# ETH-IO_v2_1.net
KiCad netlist of a schematic drawn in EAGLE
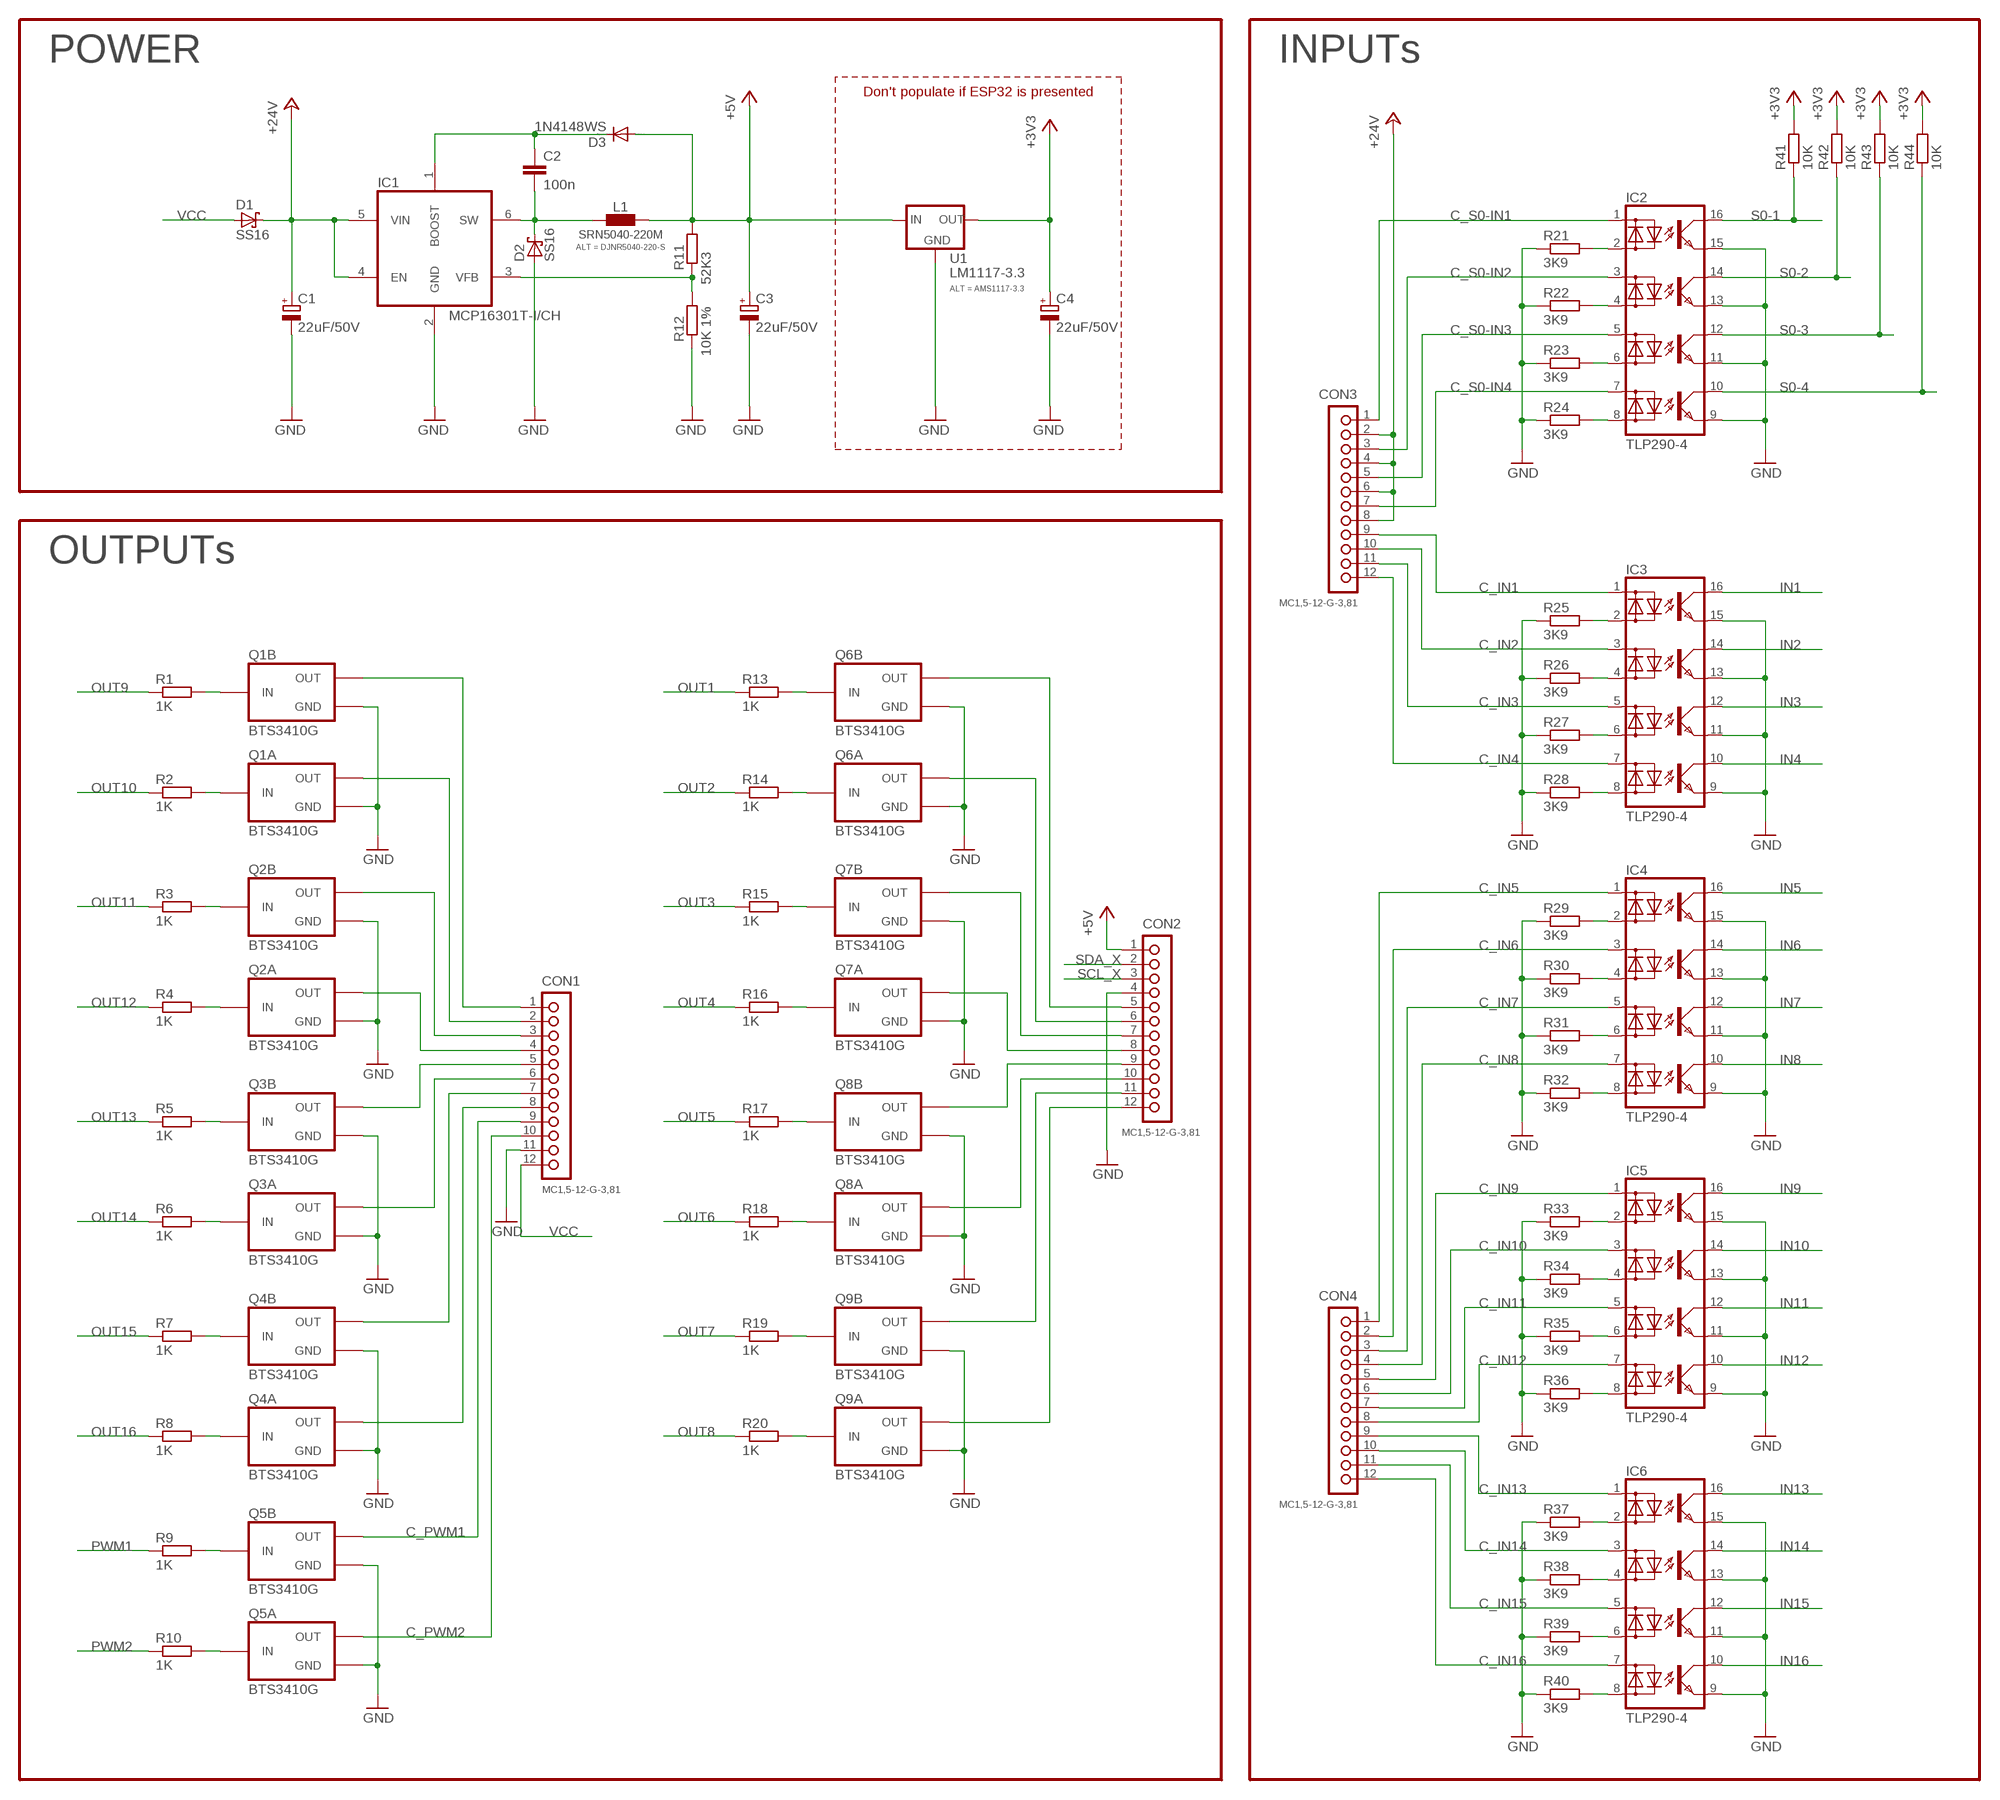
[diagram p0: schematic, sheet 1, part 1 of 2]
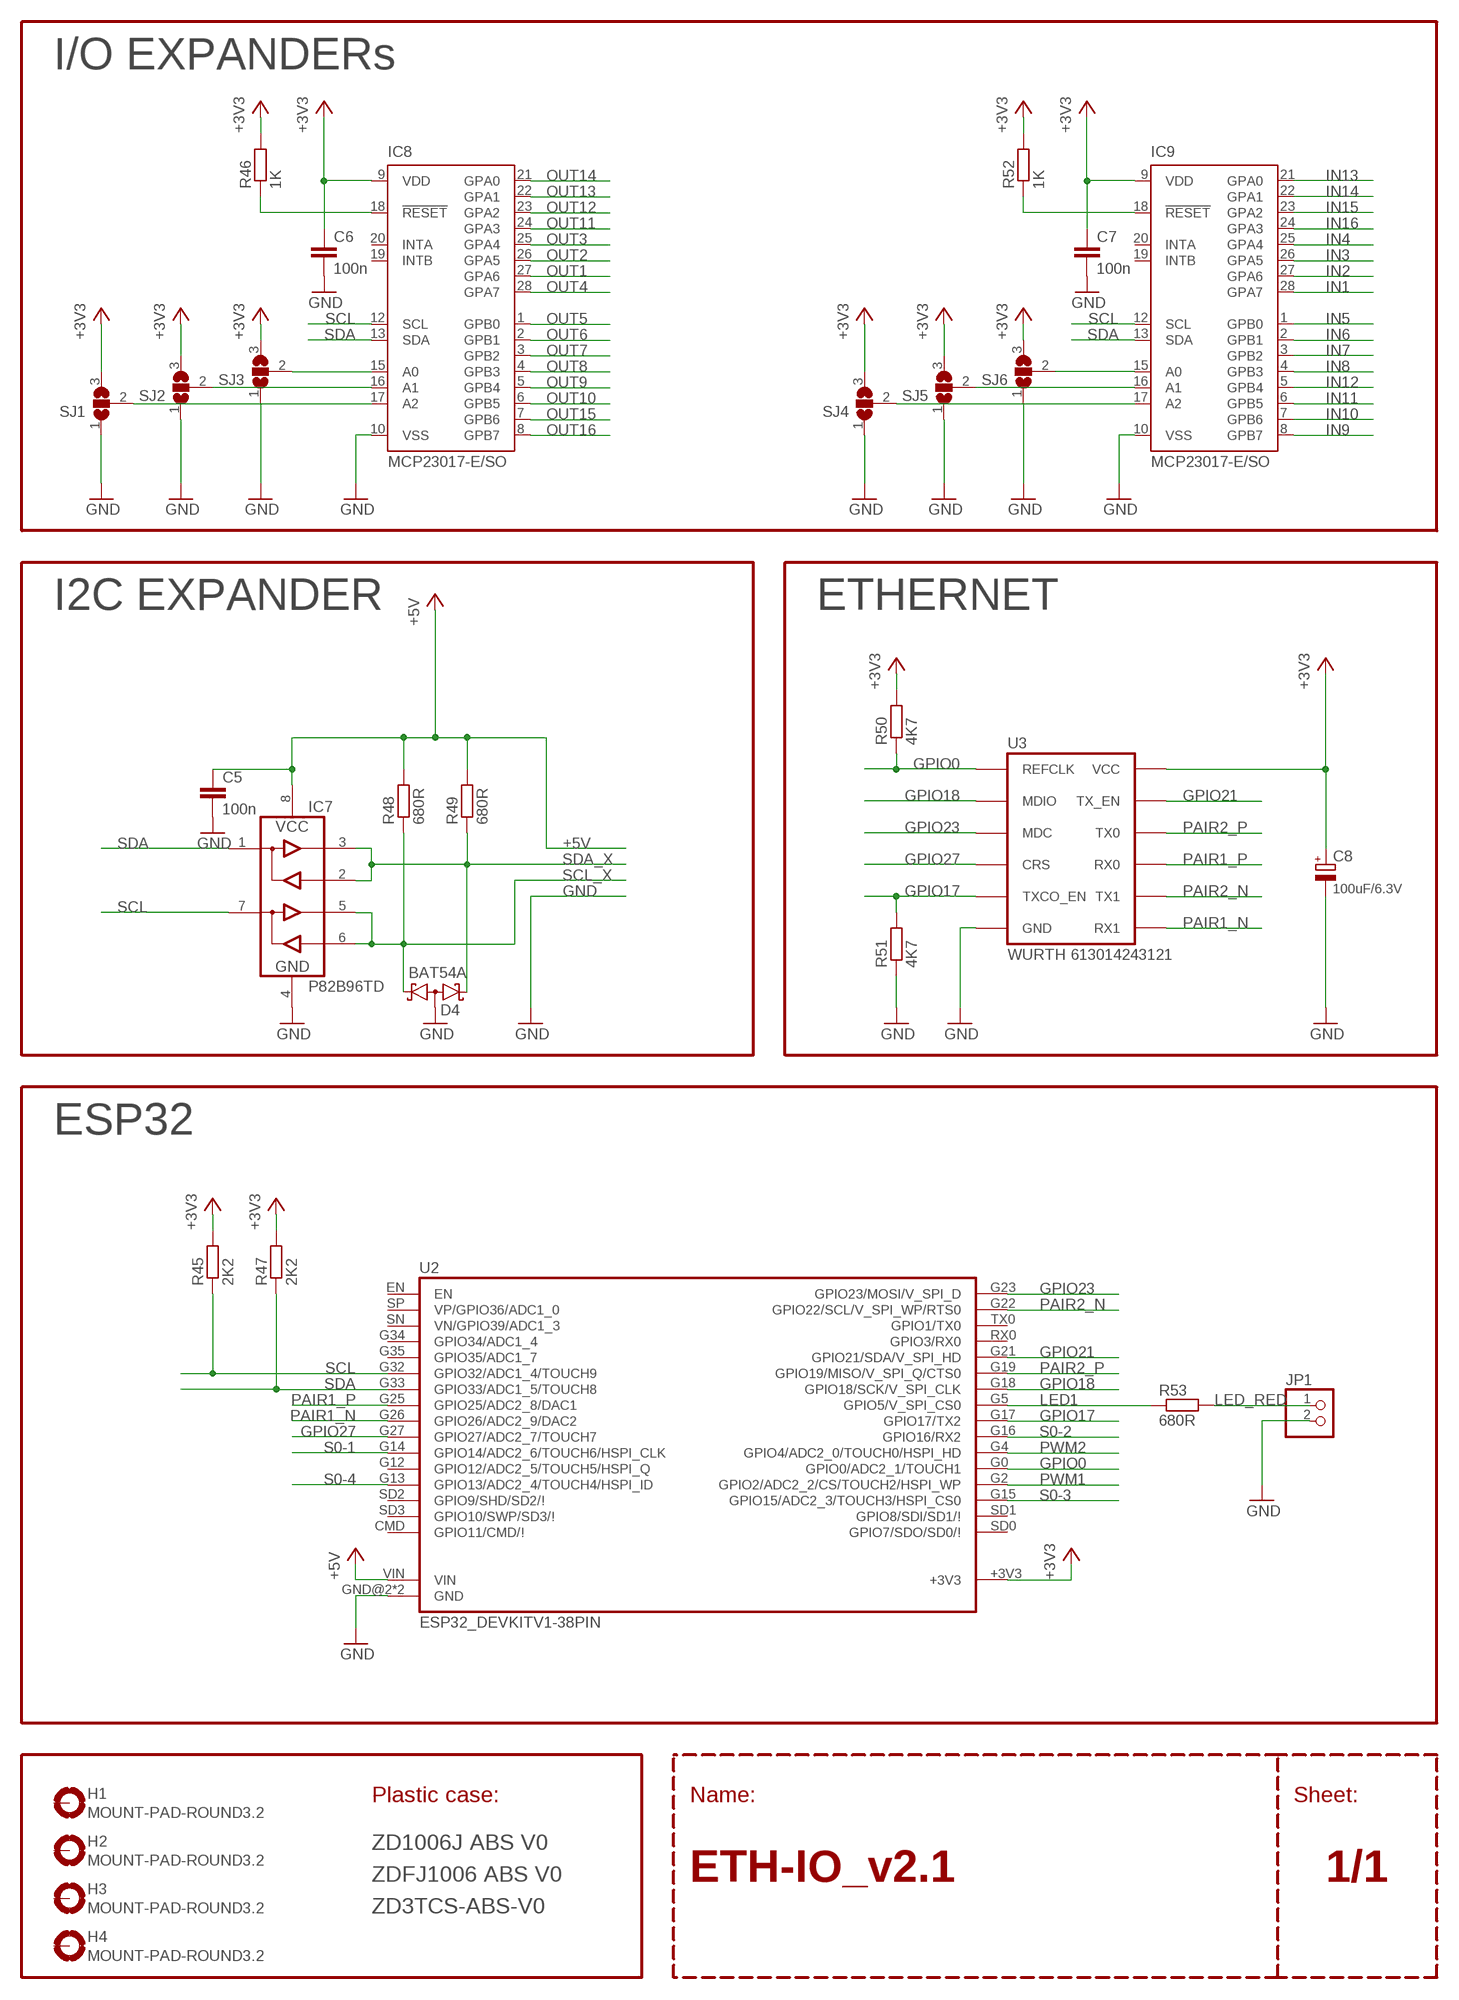
[diagram p1: schematic, sheet 1, part 2 of 2]

(export (version "E")
  (design (tool "Eeschema 10.0.6"))
  (components
    (comp (ref "C1")
      (value "22uF/50V")
      (footprint "eagle-import:PANASONIC_C")
      (libsource (lib "eagle-import") (part "CPOL-EUC"))
    )
    (comp (ref "C2")
      (value "100n")
      (footprint "eagle-import:C0805")
      (libsource (lib "eagle-import") (part "C-EUC0805"))
    )
    (comp (ref "C3")
      (value "22uF/50V")
      (footprint "eagle-import:PANASONIC_C")
      (libsource (lib "eagle-import") (part "CPOL-EUC"))
    )
    (comp (ref "C4")
      (value "22uF/50V")
      (footprint "eagle-import:PANASONIC_C")
      (libsource (lib "eagle-import") (part "CPOL-EUC"))
    )
    (comp (ref "C5")
      (value "100n")
      (footprint "eagle-import:C0805")
      (libsource (lib "eagle-import") (part "C-EUC0805"))
    )
    (comp (ref "C6")
      (value "100n")
      (footprint "eagle-import:C0805")
      (libsource (lib "eagle-import") (part "C-EUC0805"))
    )
    (comp (ref "C7")
      (value "100n")
      (footprint "eagle-import:C0805")
      (libsource (lib "eagle-import") (part "C-EUC0805"))
    )
    (comp (ref "C8")
      (value "100uF/6.3V")
      (footprint "eagle-import:PANASONIC_C")
      (libsource (lib "eagle-import") (part "CPOL-EUC"))
    )
    (comp (ref "CON1")
      (value "MC1,5-12-G-3,81")
      (footprint "eagle-import:MC1,5_12-G-3,81")
      (libsource (lib "eagle-import") (part "MC1,5-12-G-?3,81"))
    )
    (comp (ref "CON2")
      (value "MC1,5-12-G-3,81")
      (footprint "eagle-import:MC1,5_12-G-3,81")
      (libsource (lib "eagle-import") (part "MC1,5-12-G-?3,81"))
    )
    (comp (ref "CON3")
      (value "MC1,5-12-G-3,81")
      (footprint "eagle-import:MC1,5_12-G-3,81")
      (libsource (lib "eagle-import") (part "MC1,5-12-G-?3,81"))
    )
    (comp (ref "CON4")
      (value "MC1,5-12-G-3,81")
      (footprint "eagle-import:MC1,5_12-G-3,81")
      (libsource (lib "eagle-import") (part "MC1,5-12-G-?3,81"))
    )
    (comp (ref "D1")
      (value "SS16")
      (footprint "eagle-import:DO214AC")
      (libsource (lib "eagle-import") (part "SS?16"))
    )
    (comp (ref "D2")
      (value "SS16")
      (footprint "eagle-import:DO214AC")
      (libsource (lib "eagle-import") (part "SS?14"))
    )
    (comp (ref "D3")
      (value "1N4148WS")
      (footprint "eagle-import:SOD323")
      (libsource (lib "eagle-import") (part "1N4148WS"))
    )
    (comp (ref "D4")
      (value "BAT54A")
      (footprint "eagle-import:SOT23")
      (libsource (lib "eagle-import") (part "BAT54A"))
    )
    (comp (ref "H1")
      (value "MOUNT-PAD-ROUND3.2")
      (footprint "eagle-import:3,2-PAD")
      (libsource (lib "eagle-import") (part "MOUNT-PAD-ROUND3.2"))
    )
    (comp (ref "H2")
      (value "MOUNT-PAD-ROUND3.2")
      (footprint "eagle-import:3,2-PAD")
      (libsource (lib "eagle-import") (part "MOUNT-PAD-ROUND3.2"))
    )
    (comp (ref "H3")
      (value "MOUNT-PAD-ROUND3.2")
      (footprint "eagle-import:3,2-PAD")
      (libsource (lib "eagle-import") (part "MOUNT-PAD-ROUND3.2"))
    )
    (comp (ref "H4")
      (value "MOUNT-PAD-ROUND3.2")
      (footprint "eagle-import:3,2-PAD")
      (libsource (lib "eagle-import") (part "MOUNT-PAD-ROUND3.2"))
    )
    (comp (ref "IC1")
      (value "MCP16301T-I/CH")
      (footprint "eagle-import:SOT23-6")
      (libsource (lib "eagle-import") (part "MCP16301T-I/?CH"))
    )
    (comp (ref "IC2")
      (value "TLP290-4")
      (footprint "eagle-import:SO16")
      (libsource (lib "eagle-import") (part "TLP290-4"))
    )
    (comp (ref "IC3")
      (value "TLP290-4")
      (footprint "eagle-import:SO16")
      (libsource (lib "eagle-import") (part "TLP290-4"))
    )
    (comp (ref "IC4")
      (value "TLP290-4")
      (footprint "eagle-import:SO16")
      (libsource (lib "eagle-import") (part "TLP290-4"))
    )
    (comp (ref "IC5")
      (value "TLP290-4")
      (footprint "eagle-import:SO16")
      (libsource (lib "eagle-import") (part "TLP290-4"))
    )
    (comp (ref "IC6")
      (value "TLP290-4")
      (footprint "eagle-import:SO16")
      (libsource (lib "eagle-import") (part "TLP290-4"))
    )
    (comp (ref "IC7")
      (value "P82B96TD")
      (footprint "eagle-import:SO08")
      (libsource (lib "eagle-import") (part "P82B96?TD"))
    )
    (comp (ref "IC8")
      (value "MCP23017-E/SO")
      (footprint "eagle-import:SO28W")
      (fields (field (name "MF") "MICROCHIP"))
      (libsource (lib "eagle-import") (part "MCP23017SO"))
    )
    (comp (ref "IC9")
      (value "MCP23017-E/SO")
      (footprint "eagle-import:SO28W")
      (fields (field (name "MF") "MICROCHIP"))
      (libsource (lib "eagle-import") (part "MCP23017SO"))
    )
    (comp (ref "JP1")
      (value "PINHD-1X02_2.54-S")
      (footprint "eagle-import:1X02-S")
      (libsource (lib "eagle-import") (part "PINHD-1X02_2.54-S"))
    )
    (comp (ref "L1")
      (value "SRN5040-220M")
      (footprint "eagle-import:L5040")
      (fields (field (name "ALT") "DJNR5040-220-S"))
      (libsource (lib "eagle-import") (part "DJNR?-5040220"))
    )
    (comp (ref "Q1")
      (value "BTS3410G")
      (footprint "eagle-import:SO8")
      (libsource (lib "eagle-import") (part "BTS3410G"))
    )
    (comp (ref "Q2")
      (value "BTS3410G")
      (footprint "eagle-import:SO8")
      (libsource (lib "eagle-import") (part "BTS3410G"))
    )
    (comp (ref "Q3")
      (value "BTS3410G")
      (footprint "eagle-import:SO8")
      (libsource (lib "eagle-import") (part "BTS3410G"))
    )
    (comp (ref "Q4")
      (value "BTS3410G")
      (footprint "eagle-import:SO8")
      (libsource (lib "eagle-import") (part "BTS3410G"))
    )
    (comp (ref "Q5")
      (value "BTS3410G")
      (footprint "eagle-import:SO8")
      (libsource (lib "eagle-import") (part "BTS3410G"))
    )
    (comp (ref "Q6")
      (value "BTS3410G")
      (footprint "eagle-import:SO8")
      (libsource (lib "eagle-import") (part "BTS3410G"))
    )
    (comp (ref "Q7")
      (value "BTS3410G")
      (footprint "eagle-import:SO8")
      (libsource (lib "eagle-import") (part "BTS3410G"))
    )
    (comp (ref "Q8")
      (value "BTS3410G")
      (footprint "eagle-import:SO8")
      (libsource (lib "eagle-import") (part "BTS3410G"))
    )
    (comp (ref "Q9")
      (value "BTS3410G")
      (footprint "eagle-import:SO8")
      (libsource (lib "eagle-import") (part "BTS3410G"))
    )
    (comp (ref "R1")
      (value "1K")
      (footprint "eagle-import:R0805")
      (libsource (lib "eagle-import") (part "R-EU_R0805"))
    )
    (comp (ref "R2")
      (value "1K")
      (footprint "eagle-import:R0805")
      (libsource (lib "eagle-import") (part "R-EU_R0805"))
    )
    (comp (ref "R3")
      (value "1K")
      (footprint "eagle-import:R0805")
      (libsource (lib "eagle-import") (part "R-EU_R0805"))
    )
    (comp (ref "R4")
      (value "1K")
      (footprint "eagle-import:R0805")
      (libsource (lib "eagle-import") (part "R-EU_R0805"))
    )
    (comp (ref "R5")
      (value "1K")
      (footprint "eagle-import:R0805")
      (libsource (lib "eagle-import") (part "R-EU_R0805"))
    )
    (comp (ref "R6")
      (value "1K")
      (footprint "eagle-import:R0805")
      (libsource (lib "eagle-import") (part "R-EU_R0805"))
    )
    (comp (ref "R7")
      (value "1K")
      (footprint "eagle-import:R0805")
      (libsource (lib "eagle-import") (part "R-EU_R0805"))
    )
    (comp (ref "R8")
      (value "1K")
      (footprint "eagle-import:R0805")
      (libsource (lib "eagle-import") (part "R-EU_R0805"))
    )
    (comp (ref "R9")
      (value "1K")
      (footprint "eagle-import:R0805")
      (libsource (lib "eagle-import") (part "R-EU_R0805"))
    )
    (comp (ref "R10")
      (value "1K")
      (footprint "eagle-import:R0805")
      (libsource (lib "eagle-import") (part "R-EU_R0805"))
    )
    (comp (ref "R11")
      (value "52K3")
      (footprint "eagle-import:R0805")
      (libsource (lib "eagle-import") (part "R-EU_R0805"))
    )
    (comp (ref "R12")
      (value "10K 1%")
      (footprint "eagle-import:R0805")
      (libsource (lib "eagle-import") (part "R-EU_R0805"))
    )
    (comp (ref "R13")
      (value "1K")
      (footprint "eagle-import:R0805")
      (libsource (lib "eagle-import") (part "R-EU_R0805"))
    )
    (comp (ref "R14")
      (value "1K")
      (footprint "eagle-import:R0805")
      (libsource (lib "eagle-import") (part "R-EU_R0805"))
    )
    (comp (ref "R15")
      (value "1K")
      (footprint "eagle-import:R0805")
      (libsource (lib "eagle-import") (part "R-EU_R0805"))
    )
    (comp (ref "R16")
      (value "1K")
      (footprint "eagle-import:R0805")
      (libsource (lib "eagle-import") (part "R-EU_R0805"))
    )
    (comp (ref "R17")
      (value "1K")
      (footprint "eagle-import:R0805")
      (libsource (lib "eagle-import") (part "R-EU_R0805"))
    )
    (comp (ref "R18")
      (value "1K")
      (footprint "eagle-import:R0805")
      (libsource (lib "eagle-import") (part "R-EU_R0805"))
    )
    (comp (ref "R19")
      (value "1K")
      (footprint "eagle-import:R0805")
      (libsource (lib "eagle-import") (part "R-EU_R0805"))
    )
    (comp (ref "R20")
      (value "1K")
      (footprint "eagle-import:R0805")
      (libsource (lib "eagle-import") (part "R-EU_R0805"))
    )
    (comp (ref "R21")
      (value "3K9")
      (footprint "eagle-import:R0805")
      (libsource (lib "eagle-import") (part "R-EU_R0805"))
    )
    (comp (ref "R22")
      (value "3K9")
      (footprint "eagle-import:R0805")
      (libsource (lib "eagle-import") (part "R-EU_R0805"))
    )
    (comp (ref "R23")
      (value "3K9")
      (footprint "eagle-import:R0805")
      (libsource (lib "eagle-import") (part "R-EU_R0805"))
    )
    (comp (ref "R24")
      (value "3K9")
      (footprint "eagle-import:R0805")
      (libsource (lib "eagle-import") (part "R-EU_R0805"))
    )
    (comp (ref "R25")
      (value "3K9")
      (footprint "eagle-import:R0805")
      (libsource (lib "eagle-import") (part "R-EU_R0805"))
    )
    (comp (ref "R26")
      (value "3K9")
      (footprint "eagle-import:R0805")
      (libsource (lib "eagle-import") (part "R-EU_R0805"))
    )
    (comp (ref "R27")
      (value "3K9")
      (footprint "eagle-import:R0805")
      (libsource (lib "eagle-import") (part "R-EU_R0805"))
    )
    (comp (ref "R28")
      (value "3K9")
      (footprint "eagle-import:R0805")
      (libsource (lib "eagle-import") (part "R-EU_R0805"))
    )
    (comp (ref "R29")
      (value "3K9")
      (footprint "eagle-import:R0805")
      (libsource (lib "eagle-import") (part "R-EU_R0805"))
    )
    (comp (ref "R30")
      (value "3K9")
      (footprint "eagle-import:R0805")
      (libsource (lib "eagle-import") (part "R-EU_R0805"))
    )
    (comp (ref "R31")
      (value "3K9")
      (footprint "eagle-import:R0805")
      (libsource (lib "eagle-import") (part "R-EU_R0805"))
    )
    (comp (ref "R32")
      (value "3K9")
      (footprint "eagle-import:R0805")
      (libsource (lib "eagle-import") (part "R-EU_R0805"))
    )
    (comp (ref "R33")
      (value "3K9")
      (footprint "eagle-import:R0805")
      (libsource (lib "eagle-import") (part "R-EU_R0805"))
    )
    (comp (ref "R34")
      (value "3K9")
      (footprint "eagle-import:R0805")
      (libsource (lib "eagle-import") (part "R-EU_R0805"))
    )
    (comp (ref "R35")
      (value "3K9")
      (footprint "eagle-import:R0805")
      (libsource (lib "eagle-import") (part "R-EU_R0805"))
    )
    (comp (ref "R36")
      (value "3K9")
      (footprint "eagle-import:R0805")
      (libsource (lib "eagle-import") (part "R-EU_R0805"))
    )
    (comp (ref "R37")
      (value "3K9")
      (footprint "eagle-import:R0805")
      (libsource (lib "eagle-import") (part "R-EU_R0805"))
    )
    (comp (ref "R38")
      (value "3K9")
      (footprint "eagle-import:R0805")
      (libsource (lib "eagle-import") (part "R-EU_R0805"))
    )
    (comp (ref "R39")
      (value "3K9")
      (footprint "eagle-import:R0805")
      (libsource (lib "eagle-import") (part "R-EU_R0805"))
    )
    (comp (ref "R40")
      (value "3K9")
      (footprint "eagle-import:R0805")
      (libsource (lib "eagle-import") (part "R-EU_R0805"))
    )
    (comp (ref "R41")
      (value "10K")
      (footprint "eagle-import:R0805")
      (libsource (lib "eagle-import") (part "R-EU_R0805"))
    )
    (comp (ref "R42")
      (value "10K")
      (footprint "eagle-import:R0805")
      (libsource (lib "eagle-import") (part "R-EU_R0805"))
    )
    (comp (ref "R43")
      (value "10K")
      (footprint "eagle-import:R0805")
      (libsource (lib "eagle-import") (part "R-EU_R0805"))
    )
    (comp (ref "R44")
      (value "10K")
      (footprint "eagle-import:R0805")
      (libsource (lib "eagle-import") (part "R-EU_R0805"))
    )
    (comp (ref "R45")
      (value "2K2")
      (footprint "eagle-import:R0805")
      (libsource (lib "eagle-import") (part "R-EU_R0805"))
    )
    (comp (ref "R46")
      (value "1K")
      (footprint "eagle-import:R0805")
      (libsource (lib "eagle-import") (part "R-EU_R0805"))
    )
    (comp (ref "R47")
      (value "2K2")
      (footprint "eagle-import:R0805")
      (libsource (lib "eagle-import") (part "R-EU_R0805"))
    )
    (comp (ref "R48")
      (value "680R")
      (footprint "eagle-import:R0805")
      (libsource (lib "eagle-import") (part "R-EU_R0805"))
    )
    (comp (ref "R49")
      (value "680R")
      (footprint "eagle-import:R0805")
      (libsource (lib "eagle-import") (part "R-EU_R0805"))
    )
    (comp (ref "R50")
      (value "4K7")
      (footprint "eagle-import:R0805")
      (libsource (lib "eagle-import") (part "R-EU_R0805"))
    )
    (comp (ref "R51")
      (value "4K7")
      (footprint "eagle-import:R0805")
      (libsource (lib "eagle-import") (part "R-EU_R0805"))
    )
    (comp (ref "R52")
      (value "1K")
      (footprint "eagle-import:R0805")
      (libsource (lib "eagle-import") (part "R-EU_R0805"))
    )
    (comp (ref "R53")
      (value "680R")
      (footprint "eagle-import:R0805")
      (libsource (lib "eagle-import") (part "R-EU_R0805"))
    )
    (comp (ref "SJ1")
      (value "SJ2W")
      (footprint "eagle-import:SJ_2")
      (libsource (lib "eagle-import") (part "SJ2W"))
    )
    (comp (ref "SJ2")
      (value "SJ2W")
      (footprint "eagle-import:SJ_2")
      (libsource (lib "eagle-import") (part "SJ2W"))
    )
    (comp (ref "SJ3")
      (value "SJ2W")
      (footprint "eagle-import:SJ_2")
      (libsource (lib "eagle-import") (part "SJ2W"))
    )
    (comp (ref "SJ4")
      (value "SJ2W")
      (footprint "eagle-import:SJ_2")
      (libsource (lib "eagle-import") (part "SJ2W"))
    )
    (comp (ref "SJ5")
      (value "SJ2W")
      (footprint "eagle-import:SJ_2")
      (libsource (lib "eagle-import") (part "SJ2W"))
    )
    (comp (ref "SJ6")
      (value "SJ2W")
      (footprint "eagle-import:SJ_2")
      (libsource (lib "eagle-import") (part "SJ2W"))
    )
    (comp (ref "U1")
      (value "LM1117-3.3")
      (footprint "eagle-import:SOT223")
      (fields (field (name "ALT") "AMS1117-3.3"))
      (libsource (lib "eagle-import") (part "LM1117-3.3"))
    )
    (comp (ref "U2")
      (value "ESP32_DEVKITV1-38PIN")
      (footprint "eagle-import:ESP32_DEVKITV1_38PIN")
      (libsource (lib "eagle-import") (part "ESP32_DEVKITV1-38PIN"))
    )
    (comp (ref "U3")
      (value "WURTH 613014243121")
      (footprint "eagle-import:LAN8720_ETH_BOARD")
      (libsource (lib "eagle-import") (part "LAN8720_ETH_BOARD"))
    )
  )
  (nets
    (net (code "1") (name "+3V3") (class "Default")
      (node (ref "C4") (pin "+") (pinfunction "+_+") (pintype "passive"))
      (node (ref "C6") (pin "1") (pinfunction "1_1") (pintype "passive"))
      (node (ref "C7") (pin "1") (pinfunction "1_1") (pintype "passive"))
      (node (ref "C8") (pin "+") (pinfunction "+_+") (pintype "passive"))
      (node (ref "IC8") (pin "9") (pinfunction "VDD_9") (pintype "power_in"))
      (node (ref "IC9") (pin "9") (pinfunction "VDD_9") (pintype "power_in"))
      (node (ref "R41") (pin "2") (pinfunction "2_2") (pintype "passive"))
      (node (ref "R42") (pin "2") (pinfunction "2_2") (pintype "passive"))
      (node (ref "R43") (pin "2") (pinfunction "2_2") (pintype "passive"))
      (node (ref "R44") (pin "2") (pinfunction "2_2") (pintype "passive"))
      (node (ref "R45") (pin "2") (pinfunction "2_2") (pintype "passive"))
      (node (ref "R46") (pin "2") (pinfunction "2_2") (pintype "passive"))
      (node (ref "R47") (pin "2") (pinfunction "2_2") (pintype "passive"))
      (node (ref "R50") (pin "2") (pinfunction "2_2") (pintype "passive"))
      (node (ref "R52") (pin "2") (pinfunction "2_2") (pintype "passive"))
      (node (ref "SJ1") (pin "3") (pinfunction "3_3") (pintype "passive"))
      (node (ref "SJ2") (pin "3") (pinfunction "3_3") (pintype "passive"))
      (node (ref "SJ3") (pin "3") (pinfunction "3_3") (pintype "passive"))
      (node (ref "SJ4") (pin "3") (pinfunction "3_3") (pintype "passive"))
      (node (ref "SJ5") (pin "3") (pinfunction "3_3") (pintype "passive"))
      (node (ref "SJ6") (pin "3") (pinfunction "3_3") (pintype "passive"))
      (node (ref "U1") (pin "2") (pinfunction "OUT_2") (pintype "output"))
      (node (ref "U1") (pin "4") (pinfunction "OUT_4") (pintype "output"))
      (node (ref "U2") (pin "+3V3") (pinfunction "+3V3_+3V3") (pintype "power_in"))
      (node (ref "U3") (pin "VCC") (pinfunction "VCC_VCC") (pintype "power_in"))
      (node (ref "U3") (pin "VCC@1") (pinfunction "VCC_VCC@1") (pintype "power_in"))
    )
    (net (code "2") (name "+5V") (class "Default")
      (node (ref "C3") (pin "+") (pinfunction "+_+") (pintype "passive"))
      (node (ref "C5") (pin "1") (pinfunction "1_1") (pintype "passive"))
      (node (ref "CON2") (pin "1") (pinfunction "1_1") (pintype "passive"))
      (node (ref "D3") (pin "A") (pinfunction "A_A") (pintype "passive"))
      (node (ref "IC7") (pin "8") (pinfunction "VCC_8") (pintype "power_in"))
      (node (ref "L1") (pin "1") (pinfunction "1_1") (pintype "passive"))
      (node (ref "R11") (pin "2") (pinfunction "2_2") (pintype "passive"))
      (node (ref "R48") (pin "2") (pinfunction "2_2") (pintype "passive"))
      (node (ref "R49") (pin "2") (pinfunction "2_2") (pintype "passive"))
      (node (ref "U1") (pin "3") (pinfunction "IN_3") (pintype "input"))
      (node (ref "U2") (pin "VIN") (pinfunction "VIN_VIN") (pintype "power_in"))
    )
    (net (code "3") (name "+24V") (class "Default")
      (node (ref "C1") (pin "+") (pinfunction "+_+") (pintype "passive"))
      (node (ref "CON3") (pin "2") (pinfunction "2_2") (pintype "passive"))
      (node (ref "CON3") (pin "4") (pinfunction "4_4") (pintype "passive"))
      (node (ref "CON3") (pin "6") (pinfunction "6_6") (pintype "passive"))
      (node (ref "CON3") (pin "8") (pinfunction "8_8") (pintype "passive"))
      (node (ref "D1") (pin "C") (pinfunction "C_C") (pintype "passive"))
      (node (ref "IC1") (pin "4") (pinfunction "EN_4") (pintype "input"))
      (node (ref "IC1") (pin "5") (pinfunction "VIN_5") (pintype "power_in"))
    )
    (net (code "4") (name "/C_IN1") (class "Default")
      (node (ref "CON3") (pin "9") (pinfunction "9_9") (pintype "passive"))
      (node (ref "IC3") (pin "1") (pinfunction "A1_1") (pintype "passive"))
    )
    (net (code "5") (name "/C_IN2") (class "Default")
      (node (ref "CON3") (pin "10") (pinfunction "10_10") (pintype "passive"))
      (node (ref "IC3") (pin "3") (pinfunction "A2_3") (pintype "passive"))
    )
    (net (code "6") (name "/C_IN3") (class "Default")
      (node (ref "CON3") (pin "11") (pinfunction "11_11") (pintype "passive"))
      (node (ref "IC3") (pin "5") (pinfunction "A3_5") (pintype "passive"))
    )
    (net (code "7") (name "/C_IN4") (class "Default")
      (node (ref "CON3") (pin "12") (pinfunction "12_12") (pintype "passive"))
      (node (ref "IC3") (pin "7") (pinfunction "A4_7") (pintype "passive"))
    )
    (net (code "8") (name "/C_IN5") (class "Default")
      (node (ref "CON4") (pin "1") (pinfunction "1_1") (pintype "passive"))
      (node (ref "IC4") (pin "1") (pinfunction "A1_1") (pintype "passive"))
    )
    (net (code "9") (name "/C_IN6") (class "Default")
      (node (ref "CON4") (pin "2") (pinfunction "2_2") (pintype "passive"))
      (node (ref "IC4") (pin "3") (pinfunction "A2_3") (pintype "passive"))
    )
    (net (code "10") (name "/C_IN7") (class "Default")
      (node (ref "CON4") (pin "3") (pinfunction "3_3") (pintype "passive"))
      (node (ref "IC4") (pin "5") (pinfunction "A3_5") (pintype "passive"))
    )
    (net (code "11") (name "/C_IN8") (class "Default")
      (node (ref "CON4") (pin "4") (pinfunction "4_4") (pintype "passive"))
      (node (ref "IC4") (pin "7") (pinfunction "A4_7") (pintype "passive"))
    )
    (net (code "12") (name "/C_IN9") (class "Default")
      (node (ref "CON4") (pin "5") (pinfunction "5_5") (pintype "passive"))
      (node (ref "IC5") (pin "1") (pinfunction "A1_1") (pintype "passive"))
    )
    (net (code "13") (name "/C_IN10") (class "Default")
      (node (ref "CON4") (pin "6") (pinfunction "6_6") (pintype "passive"))
      (node (ref "IC5") (pin "3") (pinfunction "A2_3") (pintype "passive"))
    )
    (net (code "14") (name "/C_IN11") (class "Default")
      (node (ref "CON4") (pin "7") (pinfunction "7_7") (pintype "passive"))
      (node (ref "IC5") (pin "5") (pinfunction "A3_5") (pintype "passive"))
    )
    (net (code "15") (name "/C_IN12") (class "Default")
      (node (ref "CON4") (pin "8") (pinfunction "8_8") (pintype "passive"))
      (node (ref "IC5") (pin "7") (pinfunction "A4_7") (pintype "passive"))
    )
    (net (code "16") (name "/C_IN13") (class "Default")
      (node (ref "CON4") (pin "9") (pinfunction "9_9") (pintype "passive"))
      (node (ref "IC6") (pin "1") (pinfunction "A1_1") (pintype "passive"))
    )
    (net (code "17") (name "/C_IN14") (class "Default")
      (node (ref "CON4") (pin "10") (pinfunction "10_10") (pintype "passive"))
      (node (ref "IC6") (pin "3") (pinfunction "A2_3") (pintype "passive"))
    )
    (net (code "18") (name "/C_IN15") (class "Default")
      (node (ref "CON4") (pin "11") (pinfunction "11_11") (pintype "passive"))
      (node (ref "IC6") (pin "5") (pinfunction "A3_5") (pintype "passive"))
    )
    (net (code "19") (name "/C_IN16") (class "Default")
      (node (ref "CON4") (pin "12") (pinfunction "12_12") (pintype "passive"))
      (node (ref "IC6") (pin "7") (pinfunction "A4_7") (pintype "passive"))
    )
    (net (code "20") (name "/C_PWM1") (class "Default")
      (node (ref "CON1") (pin "9") (pinfunction "9_9") (pintype "passive"))
      (node (ref "Q5") (pin "5") (pinfunction "OUT_5") (pintype "output"))
      (node (ref "Q5") (pin "6") (pinfunction "OUT_6") (pintype "output"))
    )
    (net (code "21") (name "/C_PWM2") (class "Default")
      (node (ref "CON1") (pin "10") (pinfunction "10_10") (pintype "passive"))
      (node (ref "Q5") (pin "7") (pinfunction "OUT_7") (pintype "output"))
      (node (ref "Q5") (pin "8") (pinfunction "OUT_8") (pintype "output"))
    )
    (net (code "22") (name "/C_S0-IN1") (class "Default")
      (node (ref "CON3") (pin "1") (pinfunction "1_1") (pintype "passive"))
      (node (ref "IC2") (pin "1") (pinfunction "A1_1") (pintype "passive"))
    )
    (net (code "23") (name "/C_S0-IN2") (class "Default")
      (node (ref "CON3") (pin "3") (pinfunction "3_3") (pintype "passive"))
      (node (ref "IC2") (pin "3") (pinfunction "A2_3") (pintype "passive"))
    )
    (net (code "24") (name "/C_S0-IN3") (class "Default")
      (node (ref "CON3") (pin "5") (pinfunction "5_5") (pintype "passive"))
      (node (ref "IC2") (pin "5") (pinfunction "A3_5") (pintype "passive"))
    )
    (net (code "25") (name "/C_S0-IN4") (class "Default")
      (node (ref "CON3") (pin "7") (pinfunction "7_7") (pintype "passive"))
      (node (ref "IC2") (pin "7") (pinfunction "A4_7") (pintype "passive"))
    )
    (net (code "26") (name "/GPIO0") (class "Default")
      (node (ref "R50") (pin "1") (pinfunction "1_1") (pintype "passive"))
      (node (ref "U2") (pin "G0") (pinfunction "GPIO0/ADC2_1/TOUCH1_G0") (pintype "bidirectional"))
      (node (ref "U3") (pin "INT") (pinfunction "REFCLK_INT") (pintype "output"))
    )
    (net (code "27") (name "/GPIO17") (class "Default")
      (node (ref "R51") (pin "2") (pinfunction "2_2") (pintype "passive"))
      (node (ref "U2") (pin "G17") (pinfunction "GPIO17/TX2_G17") (pintype "output"))
      (node (ref "U3") (pin "TXCO_EN") (pinfunction "TXCO_EN_TXCO_EN") (pintype "input"))
    )
    (net (code "28") (name "/GPIO18") (class "Default")
      (node (ref "U2") (pin "G18") (pinfunction "GPIO18/SCK/V_SPI_CLK_G18") (pintype "bidirectional"))
      (node (ref "U3") (pin "MDIO") (pinfunction "MDIO_MDIO") (pintype "bidirectional"))
    )
    (net (code "29") (name "/GPIO21") (class "Default")
      (node (ref "U2") (pin "G21") (pinfunction "GPIO21/SDA/V_SPI_HD_G21") (pintype "bidirectional"))
      (node (ref "U3") (pin "TX_EN") (pinfunction "TX_EN_TX_EN") (pintype "input"))
    )
    (net (code "30") (name "/GPIO23") (class "Default")
      (node (ref "U2") (pin "G23") (pinfunction "GPIO23/MOSI/V_SPI_D_G23") (pintype "bidirectional"))
      (node (ref "U3") (pin "MDC") (pinfunction "MDC_MDC") (pintype "bidirectional"))
    )
    (net (code "31") (name "/GPIO27") (class "Default")
      (node (ref "U2") (pin "G27") (pinfunction "GPIO27/ADC2_7/TOUCH7_G27") (pintype "bidirectional"))
      (node (ref "U3") (pin "CRS") (pinfunction "CRS_CRS") (pintype "bidirectional"))
    )
    (net (code "32") (name "/IN1") (class "Default")
      (node (ref "IC3") (pin "16") (pinfunction "COL1_16") (pintype "passive"))
      (node (ref "IC9") (pin "28") (pinfunction "GPA7_28") (pintype "bidirectional"))
    )
    (net (code "33") (name "/IN2") (class "Default")
      (node (ref "IC3") (pin "14") (pinfunction "COL2_14") (pintype "passive"))
      (node (ref "IC9") (pin "27") (pinfunction "GPA6_27") (pintype "bidirectional"))
    )
    (net (code "34") (name "/IN3") (class "Default")
      (node (ref "IC3") (pin "12") (pinfunction "COL3_12") (pintype "passive"))
      (node (ref "IC9") (pin "26") (pinfunction "GPA5_26") (pintype "bidirectional"))
    )
    (net (code "35") (name "/IN4") (class "Default")
      (node (ref "IC3") (pin "10") (pinfunction "COL4_10") (pintype "passive"))
      (node (ref "IC9") (pin "25") (pinfunction "GPA4_25") (pintype "bidirectional"))
    )
    (net (code "36") (name "/IN5") (class "Default")
      (node (ref "IC4") (pin "16") (pinfunction "COL1_16") (pintype "passive"))
      (node (ref "IC9") (pin "1") (pinfunction "GPB0_1") (pintype "bidirectional"))
    )
    (net (code "37") (name "/IN6") (class "Default")
      (node (ref "IC4") (pin "14") (pinfunction "COL2_14") (pintype "passive"))
      (node (ref "IC9") (pin "2") (pinfunction "GPB1_2") (pintype "bidirectional"))
    )
    (net (code "38") (name "/IN7") (class "Default")
      (node (ref "IC4") (pin "12") (pinfunction "COL3_12") (pintype "passive"))
      (node (ref "IC9") (pin "3") (pinfunction "GPB2_3") (pintype "bidirectional"))
    )
    (net (code "39") (name "/IN8") (class "Default")
      (node (ref "IC4") (pin "10") (pinfunction "COL4_10") (pintype "passive"))
      (node (ref "IC9") (pin "4") (pinfunction "GPB3_4") (pintype "bidirectional"))
    )
    (net (code "40") (name "/IN9") (class "Default")
      (node (ref "IC5") (pin "16") (pinfunction "COL1_16") (pintype "passive"))
      (node (ref "IC9") (pin "8") (pinfunction "GPB7_8") (pintype "bidirectional"))
    )
    (net (code "41") (name "/IN10") (class "Default")
      (node (ref "IC5") (pin "14") (pinfunction "COL2_14") (pintype "passive"))
      (node (ref "IC9") (pin "7") (pinfunction "GPB6_7") (pintype "bidirectional"))
    )
    (net (code "42") (name "/IN11") (class "Default")
      (node (ref "IC5") (pin "12") (pinfunction "COL3_12") (pintype "passive"))
      (node (ref "IC9") (pin "6") (pinfunction "GPB5_6") (pintype "bidirectional"))
    )
    (net (code "43") (name "/IN12") (class "Default")
      (node (ref "IC5") (pin "10") (pinfunction "COL4_10") (pintype "passive"))
      (node (ref "IC9") (pin "5") (pinfunction "GPB4_5") (pintype "bidirectional"))
    )
    (net (code "44") (name "/IN13") (class "Default")
      (node (ref "IC6") (pin "16") (pinfunction "COL1_16") (pintype "passive"))
      (node (ref "IC9") (pin "21") (pinfunction "GPA0_21") (pintype "bidirectional"))
    )
    (net (code "45") (name "/IN14") (class "Default")
      (node (ref "IC6") (pin "14") (pinfunction "COL2_14") (pintype "passive"))
      (node (ref "IC9") (pin "22") (pinfunction "GPA1_22") (pintype "bidirectional"))
    )
    (net (code "46") (name "/IN15") (class "Default")
      (node (ref "IC6") (pin "12") (pinfunction "COL3_12") (pintype "passive"))
      (node (ref "IC9") (pin "23") (pinfunction "GPA2_23") (pintype "bidirectional"))
    )
    (net (code "47") (name "/IN16") (class "Default")
      (node (ref "IC6") (pin "10") (pinfunction "COL4_10") (pintype "passive"))
      (node (ref "IC9") (pin "24") (pinfunction "GPA3_24") (pintype "bidirectional"))
    )
    (net (code "48") (name "/LED1") (class "Default")
      (node (ref "R53") (pin "1") (pinfunction "1_1") (pintype "passive"))
      (node (ref "U2") (pin "G5") (pinfunction "GPIO5/V_SPI_CS0_G5") (pintype "bidirectional"))
    )
    (net (code "49") (name "/LED_RED") (class "Default")
      (node (ref "JP1") (pin "1") (pinfunction "1_1") (pintype "passive"))
      (node (ref "R53") (pin "2") (pinfunction "2_2") (pintype "passive"))
    )
    (net (code "50") (name "/OUT1") (class "Default")
      (node (ref "IC8") (pin "27") (pinfunction "GPA6_27") (pintype "bidirectional"))
      (node (ref "R13") (pin "1") (pinfunction "1_1") (pintype "passive"))
    )
    (net (code "51") (name "/OUT2") (class "Default")
      (node (ref "IC8") (pin "26") (pinfunction "GPA5_26") (pintype "bidirectional"))
      (node (ref "R14") (pin "1") (pinfunction "1_1") (pintype "passive"))
    )
    (net (code "52") (name "/OUT3") (class "Default")
      (node (ref "IC8") (pin "25") (pinfunction "GPA4_25") (pintype "bidirectional"))
      (node (ref "R15") (pin "1") (pinfunction "1_1") (pintype "passive"))
    )
    (net (code "53") (name "/OUT4") (class "Default")
      (node (ref "IC8") (pin "28") (pinfunction "GPA7_28") (pintype "bidirectional"))
      (node (ref "R16") (pin "1") (pinfunction "1_1") (pintype "passive"))
    )
    (net (code "54") (name "/OUT5") (class "Default")
      (node (ref "IC8") (pin "1") (pinfunction "GPB0_1") (pintype "bidirectional"))
      (node (ref "R17") (pin "1") (pinfunction "1_1") (pintype "passive"))
    )
    (net (code "55") (name "/OUT6") (class "Default")
      (node (ref "IC8") (pin "2") (pinfunction "GPB1_2") (pintype "bidirectional"))
      (node (ref "R18") (pin "1") (pinfunction "1_1") (pintype "passive"))
    )
    (net (code "56") (name "/OUT7") (class "Default")
      (node (ref "IC8") (pin "3") (pinfunction "GPB2_3") (pintype "bidirectional"))
      (node (ref "R19") (pin "1") (pinfunction "1_1") (pintype "passive"))
    )
    (net (code "57") (name "/OUT8") (class "Default")
      (node (ref "IC8") (pin "4") (pinfunction "GPB3_4") (pintype "bidirectional"))
      (node (ref "R20") (pin "1") (pinfunction "1_1") (pintype "passive"))
    )
    (net (code "58") (name "/OUT9") (class "Default")
      (node (ref "IC8") (pin "5") (pinfunction "GPB4_5") (pintype "bidirectional"))
      (node (ref "R1") (pin "1") (pinfunction "1_1") (pintype "passive"))
    )
    (net (code "59") (name "/OUT10") (class "Default")
      (node (ref "IC8") (pin "6") (pinfunction "GPB5_6") (pintype "bidirectional"))
      (node (ref "R2") (pin "1") (pinfunction "1_1") (pintype "passive"))
    )
    (net (code "60") (name "/OUT11") (class "Default")
      (node (ref "IC8") (pin "24") (pinfunction "GPA3_24") (pintype "bidirectional"))
      (node (ref "R3") (pin "1") (pinfunction "1_1") (pintype "passive"))
    )
    (net (code "61") (name "/OUT12") (class "Default")
      (node (ref "IC8") (pin "23") (pinfunction "GPA2_23") (pintype "bidirectional"))
      (node (ref "R4") (pin "1") (pinfunction "1_1") (pintype "passive"))
    )
    (net (code "62") (name "/OUT13") (class "Default")
      (node (ref "IC8") (pin "22") (pinfunction "GPA1_22") (pintype "bidirectional"))
      (node (ref "R5") (pin "1") (pinfunction "1_1") (pintype "passive"))
    )
    (net (code "63") (name "/OUT14") (class "Default")
      (node (ref "IC8") (pin "21") (pinfunction "GPA0_21") (pintype "bidirectional"))
      (node (ref "R6") (pin "1") (pinfunction "1_1") (pintype "passive"))
    )
    (net (code "64") (name "/OUT15") (class "Default")
      (node (ref "IC8") (pin "7") (pinfunction "GPB6_7") (pintype "bidirectional"))
      (node (ref "R7") (pin "1") (pinfunction "1_1") (pintype "passive"))
    )
    (net (code "65") (name "/OUT16") (class "Default")
      (node (ref "IC8") (pin "8") (pinfunction "GPB7_8") (pintype "bidirectional"))
      (node (ref "R8") (pin "1") (pinfunction "1_1") (pintype "passive"))
    )
    (net (code "66") (name "/PAIR1_N") (class "Default")
      (node (ref "U2") (pin "G26") (pinfunction "GPIO26/ADC2_9/DAC2_G26") (pintype "bidirectional"))
      (node (ref "U3") (pin "RX1") (pinfunction "RX1_RX1") (pintype "input"))
    )
    (net (code "67") (name "/PAIR1_P") (class "Default")
      (node (ref "U2") (pin "G25") (pinfunction "GPIO25/ADC2_8/DAC1_G25") (pintype "bidirectional"))
      (node (ref "U3") (pin "RX0") (pinfunction "RX0_RX0") (pintype "input"))
    )
    (net (code "68") (name "/PAIR2_N") (class "Default")
      (node (ref "U2") (pin "G22") (pinfunction "GPIO22/SCL/V_SPI_WP/RTS0_G22") (pintype "bidirectional"))
      (node (ref "U3") (pin "TX1") (pinfunction "TX1_TX1") (pintype "output"))
    )
    (net (code "69") (name "/PAIR2_P") (class "Default")
      (node (ref "U2") (pin "G19") (pinfunction "GPIO19/MISO/V_SPI_Q/CTS0_G19") (pintype "bidirectional"))
      (node (ref "U3") (pin "TX0") (pinfunction "TX0_TX0") (pintype "output"))
    )
    (net (code "70") (name "/PWM1") (class "Default")
      (node (ref "R9") (pin "1") (pinfunction "1_1") (pintype "passive"))
      (node (ref "U2") (pin "G2") (pinfunction "GPIO2/ADC2_2/CS/TOUCH2/HSPI_WP_G2") (pintype "bidirectional"))
    )
    (net (code "71") (name "/PWM2") (class "Default")
      (node (ref "R10") (pin "1") (pinfunction "1_1") (pintype "passive"))
      (node (ref "U2") (pin "G4") (pinfunction "GPIO4/ADC2_0/TOUCH0/HSPI_HD_G4") (pintype "bidirectional"))
    )
    (net (code "72") (name "/S0-1") (class "Default")
      (node (ref "IC2") (pin "16") (pinfunction "COL1_16") (pintype "passive"))
      (node (ref "R41") (pin "1") (pinfunction "1_1") (pintype "passive"))
      (node (ref "U2") (pin "G14") (pinfunction "GPIO14/ADC2_6/TOUCH6/HSPI_CLK_G14") (pintype "bidirectional"))
    )
    (net (code "73") (name "/S0-2") (class "Default")
      (node (ref "IC2") (pin "14") (pinfunction "COL2_14") (pintype "passive"))
      (node (ref "R42") (pin "1") (pinfunction "1_1") (pintype "passive"))
      (node (ref "U2") (pin "G16") (pinfunction "GPIO16/RX2_G16") (pintype "input"))
    )
    (net (code "74") (name "/S0-3") (class "Default")
      (node (ref "IC2") (pin "12") (pinfunction "COL3_12") (pintype "passive"))
      (node (ref "R43") (pin "1") (pinfunction "1_1") (pintype "passive"))
      (node (ref "U2") (pin "G15") (pinfunction "GPIO15/ADC2_3/TOUCH3/HSPI_CS0_G15") (pintype "bidirectional"))
    )
    (net (code "75") (name "/S0-4") (class "Default")
      (node (ref "IC2") (pin "10") (pinfunction "COL4_10") (pintype "passive"))
      (node (ref "R44") (pin "1") (pinfunction "1_1") (pintype "passive"))
      (node (ref "U2") (pin "G13") (pinfunction "GPIO13/ADC2_4/TOUCH4/HSPI_ID_G13") (pintype "bidirectional"))
    )
    (net (code "76") (name "/SCL") (class "Default")
      (node (ref "IC7") (pin "7") (pinfunction "SY_7") (pintype "input"))
      (node (ref "IC8") (pin "12") (pinfunction "SCL_12") (pintype "input"))
      (node (ref "IC9") (pin "12") (pinfunction "SCL_12") (pintype "input"))
      (node (ref "R45") (pin "1") (pinfunction "1_1") (pintype "passive"))
      (node (ref "U2") (pin "G32") (pinfunction "GPIO32/ADC1_4/TOUCH9_G32") (pintype "bidirectional"))
    )
    (net (code "77") (name "/SCL_X") (class "Default")
      (node (ref "CON2") (pin "3") (pinfunction "3_3") (pintype "passive"))
      (node (ref "D4") (pin "1") (pinfunction "K1_1") (pintype "passive"))
      (node (ref "IC7") (pin "5") (pinfunction "TY_5") (pintype "open_collector"))
      (node (ref "IC7") (pin "6") (pinfunction "RY_6") (pintype "open_collector"))
      (node (ref "R48") (pin "1") (pinfunction "1_1") (pintype "passive"))
    )
    (net (code "78") (name "/SDA") (class "Default")
      (node (ref "IC7") (pin "1") (pinfunction "SX_1") (pintype "input"))
      (node (ref "IC8") (pin "13") (pinfunction "SDA_13") (pintype "bidirectional"))
      (node (ref "IC9") (pin "13") (pinfunction "SDA_13") (pintype "bidirectional"))
      (node (ref "R47") (pin "1") (pinfunction "1_1") (pintype "passive"))
      (node (ref "U2") (pin "G33") (pinfunction "GPIO33/ADC1_5/TOUCH8_G33") (pintype "bidirectional"))
    )
    (net (code "79") (name "/SDA_X") (class "Default")
      (node (ref "CON2") (pin "2") (pinfunction "2_2") (pintype "passive"))
      (node (ref "D4") (pin "2") (pinfunction "K2_2") (pintype "passive"))
      (node (ref "IC7") (pin "2") (pinfunction "RX_2") (pintype "open_collector"))
      (node (ref "IC7") (pin "3") (pinfunction "TX_3") (pintype "open_collector"))
      (node (ref "R49") (pin "1") (pinfunction "1_1") (pintype "passive"))
    )
    (net (code "80") (name "/VCC") (class "Default")
      (node (ref "CON1") (pin "12") (pinfunction "12_12") (pintype "passive"))
      (node (ref "D1") (pin "A") (pinfunction "A_A") (pintype "passive"))
    )
    (net (code "81") (name "GND") (class "Default")
      (node (ref "C1") (pin "-") (pinfunction "-_-") (pintype "passive"))
      (node (ref "C3") (pin "-") (pinfunction "-_-") (pintype "passive"))
      (node (ref "C4") (pin "-") (pinfunction "-_-") (pintype "passive"))
      (node (ref "C5") (pin "2") (pinfunction "2_2") (pintype "passive"))
      (node (ref "C6") (pin "2") (pinfunction "2_2") (pintype "passive"))
      (node (ref "C7") (pin "2") (pinfunction "2_2") (pintype "passive"))
      (node (ref "C8") (pin "-") (pinfunction "-_-") (pintype "passive"))
      (node (ref "CON1") (pin "11") (pinfunction "11_11") (pintype "passive"))
      (node (ref "CON2") (pin "4") (pinfunction "4_4") (pintype "passive"))
      (node (ref "D2") (pin "A") (pinfunction "A_A") (pintype "passive"))
      (node (ref "D4") (pin "3") (pinfunction "AA_3") (pintype "passive"))
      (node (ref "IC1") (pin "2") (pinfunction "GND_2") (pintype "power_in"))
      (node (ref "IC2") (pin "11") (pinfunction "EMIT3_11") (pintype "passive"))
      (node (ref "IC2") (pin "13") (pinfunction "EMIT2_13") (pintype "passive"))
      (node (ref "IC2") (pin "15") (pinfunction "EMIT1_15") (pintype "passive"))
      (node (ref "IC2") (pin "9") (pinfunction "EMIT4_9") (pintype "passive"))
      (node (ref "IC3") (pin "11") (pinfunction "EMIT3_11") (pintype "passive"))
      (node (ref "IC3") (pin "13") (pinfunction "EMIT2_13") (pintype "passive"))
      (node (ref "IC3") (pin "15") (pinfunction "EMIT1_15") (pintype "passive"))
      (node (ref "IC3") (pin "9") (pinfunction "EMIT4_9") (pintype "passive"))
      (node (ref "IC4") (pin "11") (pinfunction "EMIT3_11") (pintype "passive"))
      (node (ref "IC4") (pin "13") (pinfunction "EMIT2_13") (pintype "passive"))
      (node (ref "IC4") (pin "15") (pinfunction "EMIT1_15") (pintype "passive"))
      (node (ref "IC4") (pin "9") (pinfunction "EMIT4_9") (pintype "passive"))
      (node (ref "IC5") (pin "11") (pinfunction "EMIT3_11") (pintype "passive"))
      (node (ref "IC5") (pin "13") (pinfunction "EMIT2_13") (pintype "passive"))
      (node (ref "IC5") (pin "15") (pinfunction "EMIT1_15") (pintype "passive"))
      (node (ref "IC5") (pin "9") (pinfunction "EMIT4_9") (pintype "passive"))
      (node (ref "IC6") (pin "11") (pinfunction "EMIT3_11") (pintype "passive"))
      (node (ref "IC6") (pin "13") (pinfunction "EMIT2_13") (pintype "passive"))
      (node (ref "IC6") (pin "15") (pinfunction "EMIT1_15") (pintype "passive"))
      (node (ref "IC6") (pin "9") (pinfunction "EMIT4_9") (pintype "passive"))
      (node (ref "IC7") (pin "4") (pinfunction "GND_4") (pintype "power_in"))
      (node (ref "IC8") (pin "10") (pinfunction "VSS_10") (pintype "power_in"))
      (node (ref "IC9") (pin "10") (pinfunction "VSS_10") (pintype "power_in"))
      (node (ref "JP1") (pin "2") (pinfunction "2_2") (pintype "passive"))
      (node (ref "Q1") (pin "1") (pinfunction "GND_1") (pintype "power_in"))
      (node (ref "Q1") (pin "3") (pinfunction "GND_3") (pintype "power_in"))
      (node (ref "Q2") (pin "1") (pinfunction "GND_1") (pintype "power_in"))
      (node (ref "Q2") (pin "3") (pinfunction "GND_3") (pintype "power_in"))
      (node (ref "Q3") (pin "1") (pinfunction "GND_1") (pintype "power_in"))
      (node (ref "Q3") (pin "3") (pinfunction "GND_3") (pintype "power_in"))
      (node (ref "Q4") (pin "1") (pinfunction "GND_1") (pintype "power_in"))
      (node (ref "Q4") (pin "3") (pinfunction "GND_3") (pintype "power_in"))
      (node (ref "Q5") (pin "1") (pinfunction "GND_1") (pintype "power_in"))
      (node (ref "Q5") (pin "3") (pinfunction "GND_3") (pintype "power_in"))
      (node (ref "Q6") (pin "1") (pinfunction "GND_1") (pintype "power_in"))
      (node (ref "Q6") (pin "3") (pinfunction "GND_3") (pintype "power_in"))
      (node (ref "Q7") (pin "1") (pinfunction "GND_1") (pintype "power_in"))
      (node (ref "Q7") (pin "3") (pinfunction "GND_3") (pintype "power_in"))
      (node (ref "Q8") (pin "1") (pinfunction "GND_1") (pintype "power_in"))
      (node (ref "Q8") (pin "3") (pinfunction "GND_3") (pintype "power_in"))
      (node (ref "Q9") (pin "1") (pinfunction "GND_1") (pintype "power_in"))
      (node (ref "Q9") (pin "3") (pinfunction "GND_3") (pintype "power_in"))
      (node (ref "R12") (pin "1") (pinfunction "1_1") (pintype "passive"))
      (node (ref "R21") (pin "1") (pinfunction "1_1") (pintype "passive"))
      (node (ref "R22") (pin "1") (pinfunction "1_1") (pintype "passive"))
      (node (ref "R23") (pin "1") (pinfunction "1_1") (pintype "passive"))
      (node (ref "R24") (pin "1") (pinfunction "1_1") (pintype "passive"))
      (node (ref "R25") (pin "1") (pinfunction "1_1") (pintype "passive"))
      (node (ref "R26") (pin "1") (pinfunction "1_1") (pintype "passive"))
      (node (ref "R27") (pin "1") (pinfunction "1_1") (pintype "passive"))
      (node (ref "R28") (pin "1") (pinfunction "1_1") (pintype "passive"))
      (node (ref "R29") (pin "1") (pinfunction "1_1") (pintype "passive"))
      (node (ref "R30") (pin "1") (pinfunction "1_1") (pintype "passive"))
      (node (ref "R31") (pin "1") (pinfunction "1_1") (pintype "passive"))
      (node (ref "R32") (pin "1") (pinfunction "1_1") (pintype "passive"))
      (node (ref "R33") (pin "1") (pinfunction "1_1") (pintype "passive"))
      (node (ref "R34") (pin "1") (pinfunction "1_1") (pintype "passive"))
      (node (ref "R35") (pin "1") (pinfunction "1_1") (pintype "passive"))
      (node (ref "R36") (pin "1") (pinfunction "1_1") (pintype "passive"))
      (node (ref "R37") (pin "1") (pinfunction "1_1") (pintype "passive"))
      (node (ref "R38") (pin "1") (pinfunction "1_1") (pintype "passive"))
      (node (ref "R39") (pin "1") (pinfunction "1_1") (pintype "passive"))
      (node (ref "R40") (pin "1") (pinfunction "1_1") (pintype "passive"))
      (node (ref "R51") (pin "1") (pinfunction "1_1") (pintype "passive"))
      (node (ref "SJ1") (pin "1") (pinfunction "1_1") (pintype "passive"))
      (node (ref "SJ2") (pin "1") (pinfunction "1_1") (pintype "passive"))
      (node (ref "SJ3") (pin "1") (pinfunction "1_1") (pintype "passive"))
      (node (ref "SJ4") (pin "1") (pinfunction "1_1") (pintype "passive"))
      (node (ref "SJ5") (pin "1") (pinfunction "1_1") (pintype "passive"))
      (node (ref "SJ6") (pin "1") (pinfunction "1_1") (pintype "passive"))
      (node (ref "U1") (pin "1") (pinfunction "GND_1") (pintype "input"))
      (node (ref "U2") (pin "GND@2") (pinfunction "GND_GND@2") (pintype "power_in"))
      (node (ref "U2") (pin "GND@3") (pinfunction "GND_GND@3") (pintype "power_in"))
      (node (ref "U3") (pin "GND") (pinfunction "GND_GND") (pintype "power_in"))
      (node (ref "U3") (pin "GND@1") (pinfunction "GND_GND@1") (pintype "power_in"))
    )
    (net (code "82") (name "Net-(CON1-Pad1)") (class "Default")
      (node (ref "CON1") (pin "1") (pinfunction "1_1") (pintype "passive"))
      (node (ref "Q1") (pin "5") (pinfunction "OUT_5") (pintype "output"))
      (node (ref "Q1") (pin "6") (pinfunction "OUT_6") (pintype "output"))
    )
    (net (code "83") (name "Net-(CON1-Pad2)") (class "Default")
      (node (ref "CON1") (pin "2") (pinfunction "2_2") (pintype "passive"))
      (node (ref "Q1") (pin "7") (pinfunction "OUT_7") (pintype "output"))
      (node (ref "Q1") (pin "8") (pinfunction "OUT_8") (pintype "output"))
    )
    (net (code "84") (name "Net-(CON1-Pad3)") (class "Default")
      (node (ref "CON1") (pin "3") (pinfunction "3_3") (pintype "passive"))
      (node (ref "Q2") (pin "5") (pinfunction "OUT_5") (pintype "output"))
      (node (ref "Q2") (pin "6") (pinfunction "OUT_6") (pintype "output"))
    )
    (net (code "85") (name "Net-(CON1-Pad4)") (class "Default")
      (node (ref "CON1") (pin "4") (pinfunction "4_4") (pintype "passive"))
      (node (ref "Q2") (pin "7") (pinfunction "OUT_7") (pintype "output"))
      (node (ref "Q2") (pin "8") (pinfunction "OUT_8") (pintype "output"))
    )
    (net (code "86") (name "Net-(CON1-Pad5)") (class "Default")
      (node (ref "CON1") (pin "5") (pinfunction "5_5") (pintype "passive"))
      (node (ref "Q3") (pin "5") (pinfunction "OUT_5") (pintype "output"))
      (node (ref "Q3") (pin "6") (pinfunction "OUT_6") (pintype "output"))
    )
    (net (code "87") (name "Net-(CON1-Pad6)") (class "Default")
      (node (ref "CON1") (pin "6") (pinfunction "6_6") (pintype "passive"))
      (node (ref "Q3") (pin "7") (pinfunction "OUT_7") (pintype "output"))
      (node (ref "Q3") (pin "8") (pinfunction "OUT_8") (pintype "output"))
    )
    (net (code "88") (name "Net-(CON1-Pad7)") (class "Default")
      (node (ref "CON1") (pin "7") (pinfunction "7_7") (pintype "passive"))
      (node (ref "Q4") (pin "5") (pinfunction "OUT_5") (pintype "output"))
      (node (ref "Q4") (pin "6") (pinfunction "OUT_6") (pintype "output"))
    )
    (net (code "89") (name "Net-(CON1-Pad8)") (class "Default")
      (node (ref "CON1") (pin "8") (pinfunction "8_8") (pintype "passive"))
      (node (ref "Q4") (pin "7") (pinfunction "OUT_7") (pintype "output"))
      (node (ref "Q4") (pin "8") (pinfunction "OUT_8") (pintype "output"))
    )
    (net (code "90") (name "Net-(CON2-Pad5)") (class "Default")
      (node (ref "CON2") (pin "5") (pinfunction "5_5") (pintype "passive"))
      (node (ref "Q6") (pin "5") (pinfunction "OUT_5") (pintype "output"))
      (node (ref "Q6") (pin "6") (pinfunction "OUT_6") (pintype "output"))
    )
    (net (code "91") (name "Net-(CON2-Pad6)") (class "Default")
      (node (ref "CON2") (pin "6") (pinfunction "6_6") (pintype "passive"))
      (node (ref "Q6") (pin "7") (pinfunction "OUT_7") (pintype "output"))
      (node (ref "Q6") (pin "8") (pinfunction "OUT_8") (pintype "output"))
    )
    (net (code "92") (name "Net-(CON2-Pad7)") (class "Default")
      (node (ref "CON2") (pin "7") (pinfunction "7_7") (pintype "passive"))
      (node (ref "Q7") (pin "5") (pinfunction "OUT_5") (pintype "output"))
      (node (ref "Q7") (pin "6") (pinfunction "OUT_6") (pintype "output"))
    )
    (net (code "93") (name "Net-(CON2-Pad8)") (class "Default")
      (node (ref "CON2") (pin "8") (pinfunction "8_8") (pintype "passive"))
      (node (ref "Q7") (pin "7") (pinfunction "OUT_7") (pintype "output"))
      (node (ref "Q7") (pin "8") (pinfunction "OUT_8") (pintype "output"))
    )
    (net (code "94") (name "Net-(CON2-Pad9)") (class "Default")
      (node (ref "CON2") (pin "9") (pinfunction "9_9") (pintype "passive"))
      (node (ref "Q8") (pin "5") (pinfunction "OUT_5") (pintype "output"))
      (node (ref "Q8") (pin "6") (pinfunction "OUT_6") (pintype "output"))
    )
    (net (code "95") (name "Net-(CON2-Pad10)") (class "Default")
      (node (ref "CON2") (pin "10") (pinfunction "10_10") (pintype "passive"))
      (node (ref "Q8") (pin "7") (pinfunction "OUT_7") (pintype "output"))
      (node (ref "Q8") (pin "8") (pinfunction "OUT_8") (pintype "output"))
    )
    (net (code "96") (name "Net-(CON2-Pad11)") (class "Default")
      (node (ref "CON2") (pin "11") (pinfunction "11_11") (pintype "passive"))
      (node (ref "Q9") (pin "5") (pinfunction "OUT_5") (pintype "output"))
      (node (ref "Q9") (pin "6") (pinfunction "OUT_6") (pintype "output"))
    )
    (net (code "97") (name "Net-(CON2-Pad12)") (class "Default")
      (node (ref "CON2") (pin "12") (pinfunction "12_12") (pintype "passive"))
      (node (ref "Q9") (pin "7") (pinfunction "OUT_7") (pintype "output"))
      (node (ref "Q9") (pin "8") (pinfunction "OUT_8") (pintype "output"))
    )
    (net (code "98") (name "Net-(IC1-BOOST)") (class "Default")
      (node (ref "C2") (pin "1") (pinfunction "1_1") (pintype "passive"))
      (node (ref "D3") (pin "C") (pinfunction "C_C") (pintype "passive"))
      (node (ref "IC1") (pin "1") (pinfunction "BOOST_1") (pintype "passive"))
    )
    (net (code "99") (name "Net-(IC1-SW)") (class "Default")
      (node (ref "C2") (pin "2") (pinfunction "2_2") (pintype "passive"))
      (node (ref "D2") (pin "C") (pinfunction "C_C") (pintype "passive"))
      (node (ref "IC1") (pin "6") (pinfunction "SW_6") (pintype "output"))
      (node (ref "L1") (pin "2") (pinfunction "2_2") (pintype "passive"))
    )
    (net (code "100") (name "Net-(IC1-VFB)") (class "Default")
      (node (ref "IC1") (pin "3") (pinfunction "VFB_3") (pintype "input"))
      (node (ref "R11") (pin "1") (pinfunction "1_1") (pintype "passive"))
      (node (ref "R12") (pin "2") (pinfunction "2_2") (pintype "passive"))
    )
    (net (code "101") (name "Net-(IC2-C1)") (class "Default")
      (node (ref "IC2") (pin "2") (pinfunction "C1_2") (pintype "passive"))
      (node (ref "R21") (pin "2") (pinfunction "2_2") (pintype "passive"))
    )
    (net (code "102") (name "Net-(IC2-C2)") (class "Default")
      (node (ref "IC2") (pin "4") (pinfunction "C2_4") (pintype "passive"))
      (node (ref "R22") (pin "2") (pinfunction "2_2") (pintype "passive"))
    )
    (net (code "103") (name "Net-(IC2-C3)") (class "Default")
      (node (ref "IC2") (pin "6") (pinfunction "C3_6") (pintype "passive"))
      (node (ref "R23") (pin "2") (pinfunction "2_2") (pintype "passive"))
    )
    (net (code "104") (name "Net-(IC2-C4)") (class "Default")
      (node (ref "IC2") (pin "8") (pinfunction "C4_8") (pintype "passive"))
      (node (ref "R24") (pin "2") (pinfunction "2_2") (pintype "passive"))
    )
    (net (code "105") (name "Net-(IC3-C1)") (class "Default")
      (node (ref "IC3") (pin "2") (pinfunction "C1_2") (pintype "passive"))
      (node (ref "R25") (pin "2") (pinfunction "2_2") (pintype "passive"))
    )
    (net (code "106") (name "Net-(IC3-C2)") (class "Default")
      (node (ref "IC3") (pin "4") (pinfunction "C2_4") (pintype "passive"))
      (node (ref "R26") (pin "2") (pinfunction "2_2") (pintype "passive"))
    )
    (net (code "107") (name "Net-(IC3-C3)") (class "Default")
      (node (ref "IC3") (pin "6") (pinfunction "C3_6") (pintype "passive"))
      (node (ref "R27") (pin "2") (pinfunction "2_2") (pintype "passive"))
    )
    (net (code "108") (name "Net-(IC3-C4)") (class "Default")
      (node (ref "IC3") (pin "8") (pinfunction "C4_8") (pintype "passive"))
      (node (ref "R28") (pin "2") (pinfunction "2_2") (pintype "passive"))
    )
    (net (code "109") (name "Net-(IC4-C1)") (class "Default")
      (node (ref "IC4") (pin "2") (pinfunction "C1_2") (pintype "passive"))
      (node (ref "R29") (pin "2") (pinfunction "2_2") (pintype "passive"))
    )
    (net (code "110") (name "Net-(IC4-C2)") (class "Default")
      (node (ref "IC4") (pin "4") (pinfunction "C2_4") (pintype "passive"))
      (node (ref "R30") (pin "2") (pinfunction "2_2") (pintype "passive"))
    )
    (net (code "111") (name "Net-(IC4-C3)") (class "Default")
      (node (ref "IC4") (pin "6") (pinfunction "C3_6") (pintype "passive"))
      (node (ref "R31") (pin "2") (pinfunction "2_2") (pintype "passive"))
    )
    (net (code "112") (name "Net-(IC4-C4)") (class "Default")
      (node (ref "IC4") (pin "8") (pinfunction "C4_8") (pintype "passive"))
      (node (ref "R32") (pin "2") (pinfunction "2_2") (pintype "passive"))
    )
    (net (code "113") (name "Net-(IC5-C1)") (class "Default")
      (node (ref "IC5") (pin "2") (pinfunction "C1_2") (pintype "passive"))
      (node (ref "R33") (pin "2") (pinfunction "2_2") (pintype "passive"))
    )
    (net (code "114") (name "Net-(IC5-C2)") (class "Default")
      (node (ref "IC5") (pin "4") (pinfunction "C2_4") (pintype "passive"))
      (node (ref "R34") (pin "2") (pinfunction "2_2") (pintype "passive"))
    )
    (net (code "115") (name "Net-(IC5-C3)") (class "Default")
      (node (ref "IC5") (pin "6") (pinfunction "C3_6") (pintype "passive"))
      (node (ref "R35") (pin "2") (pinfunction "2_2") (pintype "passive"))
    )
    (net (code "116") (name "Net-(IC5-C4)") (class "Default")
      (node (ref "IC5") (pin "8") (pinfunction "C4_8") (pintype "passive"))
      (node (ref "R36") (pin "2") (pinfunction "2_2") (pintype "passive"))
    )
    (net (code "117") (name "Net-(IC6-C1)") (class "Default")
      (node (ref "IC6") (pin "2") (pinfunction "C1_2") (pintype "passive"))
      (node (ref "R37") (pin "2") (pinfunction "2_2") (pintype "passive"))
    )
    (net (code "118") (name "Net-(IC6-C2)") (class "Default")
      (node (ref "IC6") (pin "4") (pinfunction "C2_4") (pintype "passive"))
      (node (ref "R38") (pin "2") (pinfunction "2_2") (pintype "passive"))
    )
    (net (code "119") (name "Net-(IC6-C3)") (class "Default")
      (node (ref "IC6") (pin "6") (pinfunction "C3_6") (pintype "passive"))
      (node (ref "R39") (pin "2") (pinfunction "2_2") (pintype "passive"))
    )
    (net (code "120") (name "Net-(IC6-C4)") (class "Default")
      (node (ref "IC6") (pin "8") (pinfunction "C4_8") (pintype "passive"))
      (node (ref "R40") (pin "2") (pinfunction "2_2") (pintype "passive"))
    )
    (net (code "121") (name "Net-(IC8-A0)") (class "Default")
      (node (ref "IC8") (pin "15") (pinfunction "A0_15") (pintype "input"))
      (node (ref "SJ3") (pin "2") (pinfunction "2_2") (pintype "passive"))
    )
    (net (code "122") (name "Net-(IC8-A1)") (class "Default")
      (node (ref "IC8") (pin "16") (pinfunction "A1_16") (pintype "input"))
      (node (ref "SJ2") (pin "2") (pinfunction "2_2") (pintype "passive"))
    )
    (net (code "123") (name "Net-(IC8-A2)") (class "Default")
      (node (ref "IC8") (pin "17") (pinfunction "A2_17") (pintype "input"))
      (node (ref "SJ1") (pin "2") (pinfunction "2_2") (pintype "passive"))
    )
    (net (code "124") (name "Net-(IC8-~{RESET})") (class "Default")
      (node (ref "IC8") (pin "18") (pinfunction "~{RESET}_18") (pintype "input"))
      (node (ref "R46") (pin "1") (pinfunction "1_1") (pintype "passive"))
    )
    (net (code "125") (name "Net-(IC9-A0)") (class "Default")
      (node (ref "IC9") (pin "15") (pinfunction "A0_15") (pintype "input"))
      (node (ref "SJ6") (pin "2") (pinfunction "2_2") (pintype "passive"))
    )
    (net (code "126") (name "Net-(IC9-A1)") (class "Default")
      (node (ref "IC9") (pin "16") (pinfunction "A1_16") (pintype "input"))
      (node (ref "SJ5") (pin "2") (pinfunction "2_2") (pintype "passive"))
    )
    (net (code "127") (name "Net-(IC9-A2)") (class "Default")
      (node (ref "IC9") (pin "17") (pinfunction "A2_17") (pintype "input"))
      (node (ref "SJ4") (pin "2") (pinfunction "2_2") (pintype "passive"))
    )
    (net (code "128") (name "Net-(IC9-~{RESET})") (class "Default")
      (node (ref "IC9") (pin "18") (pinfunction "~{RESET}_18") (pintype "input"))
      (node (ref "R52") (pin "1") (pinfunction "1_1") (pintype "passive"))
    )
    (net (code "129") (name "Net-(Q1A-IN)") (class "Default")
      (node (ref "Q1") (pin "2") (pinfunction "IN_2") (pintype "input"))
      (node (ref "R2") (pin "2") (pinfunction "2_2") (pintype "passive"))
    )
    (net (code "130") (name "Net-(Q1B-IN)") (class "Default")
      (node (ref "Q1") (pin "4") (pinfunction "IN_4") (pintype "input"))
      (node (ref "R1") (pin "2") (pinfunction "2_2") (pintype "passive"))
    )
    (net (code "131") (name "Net-(Q2A-IN)") (class "Default")
      (node (ref "Q2") (pin "2") (pinfunction "IN_2") (pintype "input"))
      (node (ref "R4") (pin "2") (pinfunction "2_2") (pintype "passive"))
    )
    (net (code "132") (name "Net-(Q2B-IN)") (class "Default")
      (node (ref "Q2") (pin "4") (pinfunction "IN_4") (pintype "input"))
      (node (ref "R3") (pin "2") (pinfunction "2_2") (pintype "passive"))
    )
    (net (code "133") (name "Net-(Q3A-IN)") (class "Default")
      (node (ref "Q3") (pin "2") (pinfunction "IN_2") (pintype "input"))
      (node (ref "R6") (pin "2") (pinfunction "2_2") (pintype "passive"))
    )
    (net (code "134") (name "Net-(Q3B-IN)") (class "Default")
      (node (ref "Q3") (pin "4") (pinfunction "IN_4") (pintype "input"))
      (node (ref "R5") (pin "2") (pinfunction "2_2") (pintype "passive"))
    )
    (net (code "135") (name "Net-(Q4A-IN)") (class "Default")
      (node (ref "Q4") (pin "2") (pinfunction "IN_2") (pintype "input"))
      (node (ref "R8") (pin "2") (pinfunction "2_2") (pintype "passive"))
    )
    (net (code "136") (name "Net-(Q4B-IN)") (class "Default")
      (node (ref "Q4") (pin "4") (pinfunction "IN_4") (pintype "input"))
      (node (ref "R7") (pin "2") (pinfunction "2_2") (pintype "passive"))
    )
    (net (code "137") (name "Net-(Q5A-IN)") (class "Default")
      (node (ref "Q5") (pin "2") (pinfunction "IN_2") (pintype "input"))
      (node (ref "R10") (pin "2") (pinfunction "2_2") (pintype "passive"))
    )
    (net (code "138") (name "Net-(Q5B-IN)") (class "Default")
      (node (ref "Q5") (pin "4") (pinfunction "IN_4") (pintype "input"))
      (node (ref "R9") (pin "2") (pinfunction "2_2") (pintype "passive"))
    )
    (net (code "139") (name "Net-(Q6A-IN)") (class "Default")
      (node (ref "Q6") (pin "2") (pinfunction "IN_2") (pintype "input"))
      (node (ref "R14") (pin "2") (pinfunction "2_2") (pintype "passive"))
    )
    (net (code "140") (name "Net-(Q6B-IN)") (class "Default")
      (node (ref "Q6") (pin "4") (pinfunction "IN_4") (pintype "input"))
      (node (ref "R13") (pin "2") (pinfunction "2_2") (pintype "passive"))
    )
    (net (code "141") (name "Net-(Q7A-IN)") (class "Default")
      (node (ref "Q7") (pin "2") (pinfunction "IN_2") (pintype "input"))
      (node (ref "R16") (pin "2") (pinfunction "2_2") (pintype "passive"))
    )
    (net (code "142") (name "Net-(Q7B-IN)") (class "Default")
      (node (ref "Q7") (pin "4") (pinfunction "IN_4") (pintype "input"))
      (node (ref "R15") (pin "2") (pinfunction "2_2") (pintype "passive"))
    )
    (net (code "143") (name "Net-(Q8A-IN)") (class "Default")
      (node (ref "Q8") (pin "2") (pinfunction "IN_2") (pintype "input"))
      (node (ref "R18") (pin "2") (pinfunction "2_2") (pintype "passive"))
    )
    (net (code "144") (name "Net-(Q8B-IN)") (class "Default")
      (node (ref "Q8") (pin "4") (pinfunction "IN_4") (pintype "input"))
      (node (ref "R17") (pin "2") (pinfunction "2_2") (pintype "passive"))
    )
    (net (code "145") (name "Net-(Q9A-IN)") (class "Default")
      (node (ref "Q9") (pin "2") (pinfunction "IN_2") (pintype "input"))
      (node (ref "R20") (pin "2") (pinfunction "2_2") (pintype "passive"))
    )
    (net (code "146") (name "Net-(Q9B-IN)") (class "Default")
      (node (ref "Q9") (pin "4") (pinfunction "IN_4") (pintype "input"))
      (node (ref "R19") (pin "2") (pinfunction "2_2") (pintype "passive"))
    )
    (net (code "147") (name "unconnected-(H1-MOUNT-PadB3,2)") (class "Default")
      (node (ref "H1") (pin "B3,2") (pinfunction "MOUNT_B3,2") (pintype "passive"))
    )
    (net (code "148") (name "unconnected-(H2-MOUNT-PadB3,2)") (class "Default")
      (node (ref "H2") (pin "B3,2") (pinfunction "MOUNT_B3,2") (pintype "passive"))
    )
    (net (code "149") (name "unconnected-(H3-MOUNT-PadB3,2)") (class "Default")
      (node (ref "H3") (pin "B3,2") (pinfunction "MOUNT_B3,2") (pintype "passive"))
    )
    (net (code "150") (name "unconnected-(H4-MOUNT-PadB3,2)") (class "Default")
      (node (ref "H4") (pin "B3,2") (pinfunction "MOUNT_B3,2") (pintype "passive"))
    )
    (net (code "151") (name "unconnected-(IC8-INTA-Pad20)") (class "Default")
      (node (ref "IC8") (pin "20") (pinfunction "INTA_20") (pintype "output"))
    )
    (net (code "152") (name "unconnected-(IC8-INTB-Pad19)") (class "Default")
      (node (ref "IC8") (pin "19") (pinfunction "INTB_19") (pintype "output"))
    )
    (net (code "153") (name "unconnected-(IC9-INTA-Pad20)") (class "Default")
      (node (ref "IC9") (pin "20") (pinfunction "INTA_20") (pintype "output"))
    )
    (net (code "154") (name "unconnected-(IC9-INTB-Pad19)") (class "Default")
      (node (ref "IC9") (pin "19") (pinfunction "INTB_19") (pintype "output"))
    )
    (net (code "155") (name "unconnected-(U2-GPIO1{slash}TX0-PadTX0)") (class "Default")
      (node (ref "U2") (pin "TX0") (pinfunction "GPIO1/TX0_TX0") (pintype "output"))
    )
    (net (code "156") (name "unconnected-(U2-GPIO3{slash}RX0-PadRX0)") (class "Default")
      (node (ref "U2") (pin "RX0") (pinfunction "GPIO3/RX0_RX0") (pintype "input"))
    )
    (net (code "157") (name "unconnected-(U2-GPIO7{slash}SDO{slash}SD0{slash}~{}-PadSD0)") (class "Default")
      (node (ref "U2") (pin "SD0") (pinfunction "GPIO7/SDO/SD0/~{}_SD0") (pintype "bidirectional"))
    )
    (net (code "158") (name "unconnected-(U2-GPIO8{slash}SDI{slash}SD1{slash}~{}-PadSD1)") (class "Default")
      (node (ref "U2") (pin "SD1") (pinfunction "GPIO8/SDI/SD1/~{}_SD1") (pintype "bidirectional"))
    )
    (net (code "159") (name "unconnected-(U2-GPIO9{slash}SHD{slash}SD2{slash}~{}-PadSD2)") (class "Default")
      (node (ref "U2") (pin "SD2") (pinfunction "GPIO9/SHD/SD2/~{}_SD2") (pintype "bidirectional"))
    )
    (net (code "160") (name "unconnected-(U2-GPIO10{slash}SWP{slash}SD3{slash}~{}-PadSD3)") (class "Default")
      (node (ref "U2") (pin "SD3") (pinfunction "GPIO10/SWP/SD3/~{}_SD3") (pintype "bidirectional"))
    )
    (net (code "161") (name "unconnected-(U2-GPIO11{slash}CMD{slash}~{}-PadCMD)") (class "Default")
      (node (ref "U2") (pin "CMD") (pinfunction "GPIO11/CMD/~{}_CMD") (pintype "bidirectional"))
    )
    (net (code "162") (name "unconnected-(U2-GPIO12{slash}ADC2_5{slash}TOUCH5{slash}HSPI_Q-PadG12)") (class "Default")
      (node (ref "U2") (pin "G12") (pinfunction "GPIO12/ADC2_5/TOUCH5/HSPI_Q_G12") (pintype "bidirectional"))
    )
    (net (code "163") (name "unconnected-(U2-GPIO34{slash}ADC1_4-PadG34)") (class "Default")
      (node (ref "U2") (pin "G34") (pinfunction "GPIO34/ADC1_4_G34") (pintype "bidirectional"))
    )
    (net (code "164") (name "unconnected-(U2-GPIO35{slash}ADC1_7-PadG35)") (class "Default")
      (node (ref "U2") (pin "G35") (pinfunction "GPIO35/ADC1_7_G35") (pintype "bidirectional"))
    )
    (net (code "165") (name "unconnected-(U2-PadEN)") (class "Default")
      (node (ref "U2") (pin "EN") (pinfunction "EN_EN") (pintype "input"))
    )
    (net (code "166") (name "unconnected-(U2-VN{slash}GPIO39{slash}ADC1_3-PadSN)") (class "Default")
      (node (ref "U2") (pin "SN") (pinfunction "VN/GPIO39/ADC1_3_SN") (pintype "bidirectional"))
    )
    (net (code "167") (name "unconnected-(U2-VP{slash}GPIO36{slash}ADC1_0-PadSP)") (class "Default")
      (node (ref "U2") (pin "SP") (pinfunction "VP/GPIO36/ADC1_0_SP") (pintype "bidirectional"))
    )
  )
)
